# Display.net
KiCad netlist of a schematic drawn in Altium Designer
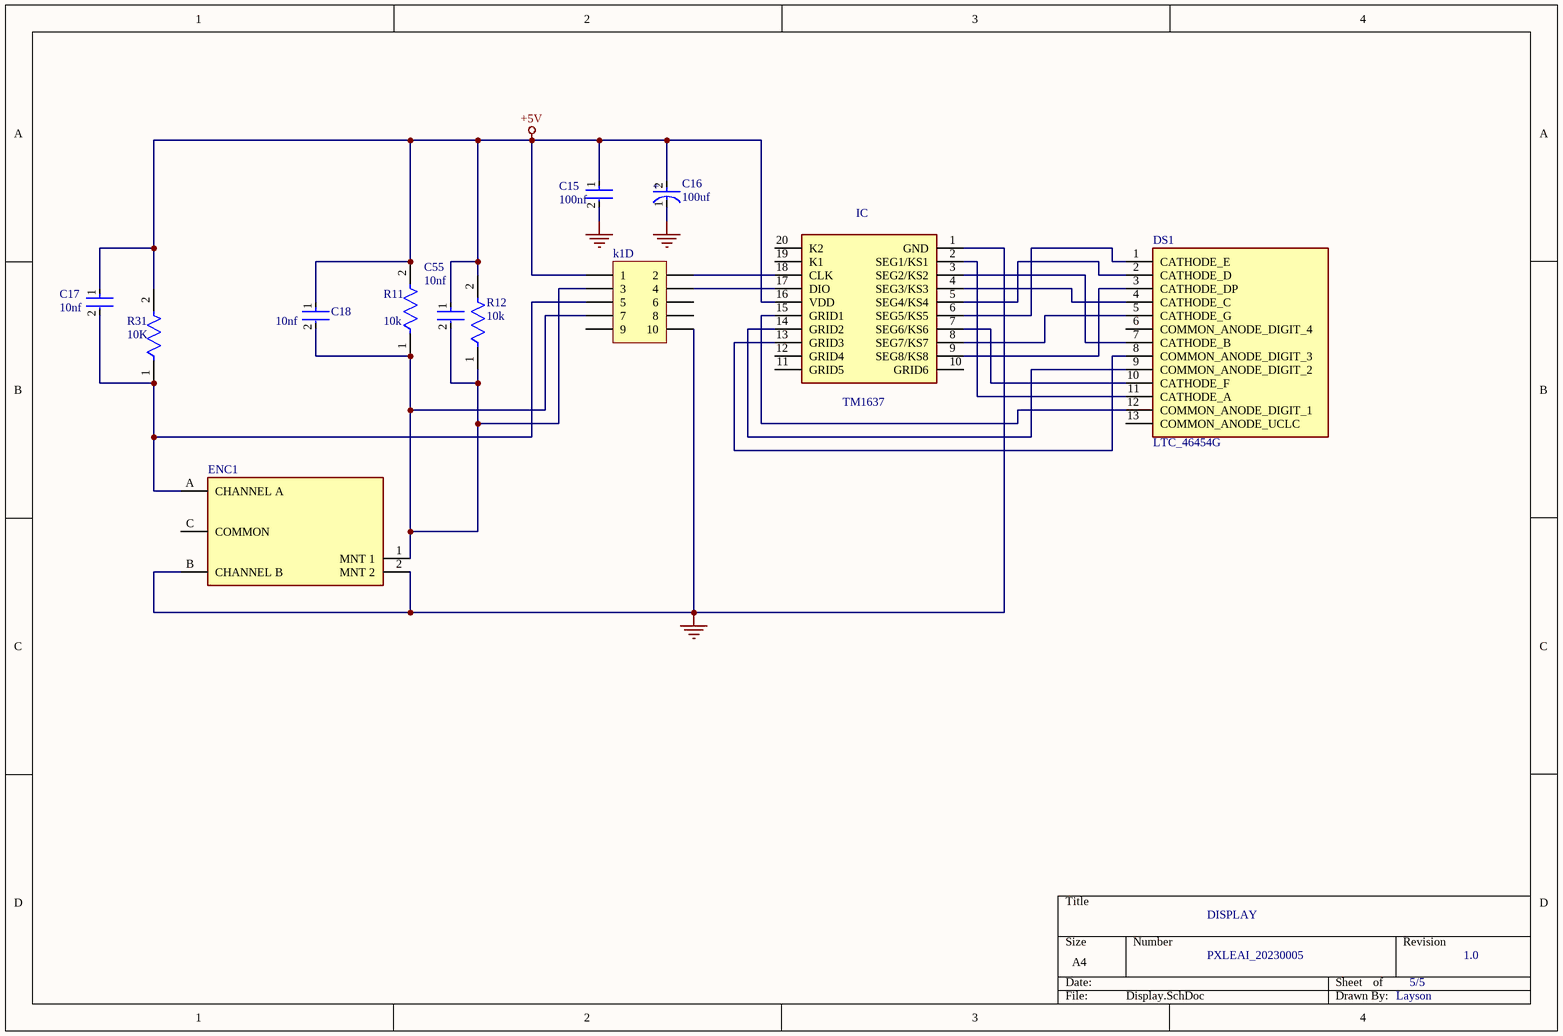
[diagram p0: Display.SchDoc]

(export (version "E")
  (design (tool "Eeschema 10.0.6"))
  (components
    (comp (ref "C15")
      (value "100nf")
      (footprint "FP-C320C-MFG")
      (description "CAP CER 0.1UF 50V X7R RADIAL")
      (fields (field (name "TOLERANCE") "5%") (field (name "MANUFACTURER PART NUMBER") "C320C104J5R5TA7301"))
      (libsource (lib "Altium Content Vault") (part "11868f565c42a9108669ba33697ecf6"))
    )
    (comp (ref "C16")
      (value "100uf")
      (footprint "FP-RAD-TH-D_8_0_5-L_11_5-MFG")
      (description "Aluminum Electrolytic Capacitors (Radial Lead Type) 100uF ±20% 50V")
      (fields (field (name "VOLTAGE") "50V") (field (name "TOLERANCE") "20%"))
      (libsource (lib "Altium Content Vault") (part "a00bbbee19879c290e62620ae7e47b1"))
    )
    (comp (ref "C17")
      (value "10nf")
      (footprint "FP-RDE0M1-MFG")
      (description "Ceramic Capacitor 10nF ±10% 50V X7R Radial")
      (fields (field (name "TOLERANCE") "10%"))
      (libsource (lib "Altium Content Vault") (part "b4654b650e69147ec39a6b967a45e02"))
    )
    (comp (ref "C18")
      (value "10nf")
      (footprint "FP-RDE0M1-MFG")
      (description "Ceramic Capacitor 10nF ±10% 50V X7R Radial")
      (fields (field (name "TOLERANCE") "10%"))
      (libsource (lib "Altium Content Vault") (part "b4654b650e69147ec39a6b967a45e02"))
    )
    (comp (ref "C55")
      (value "10nf")
      (footprint "FP-RDE0M1-MFG")
      (description "Ceramic Capacitor 10nF ±10% 50V X7R Radial")
      (fields (field (name "TOLERANCE") "10%"))
      (libsource (lib "Altium Content Vault") (part "b4654b650e69147ec39a6b967a45e02"))
    )
    (comp (ref "DS1")
      (value "LTC_46454G")
      (footprint "SamacSys:LTC46454G")
      (description "Display")
      (fields (field (name "MANUFACTURER_PART_NUMBER") "LTC 46454G"))
      (libsource (lib "*") (part "LTC_46454G"))
    )
    (comp (ref "ENC1")
      (value "PEC11R-4015F-N0024")
      (footprint "FP-PEC11R-4015F-N0024-MFG")
      (description "ROTARY ENCODER MECHANICAL 24PPR")
      (fields
        (field (name "MANUFACTURER") "Bourns")
        (field (name "OCTOPART") "https://octopart.com/pec11r-4015f-n0024-bourns-26648251")
      )
      (libsource (lib "Altium Content Vault") (part "714335eeadb64c170d88fa1cfc7421d"))
    )
    (comp (ref "IC")
      (value "TM1637")
      (footprint "SOIC127P1045X280-20N")
      (description "LED Drive Control Special Circuit")
      (fields (field (name "MANUFACTURER_PART_NUMBER") "TM1637 (SOP)"))
      (libsource (lib "Soldeerstation") (part "TM1637__SOP_"))
    )
    (comp (ref "k1D")
      (value "Header 5X2")
      (footprint "HDR2X5")
      (description "Header, 5-Pin, Dual row")
      (fields (field (name "PUBLISHER") "Altium Limited"))
      (libsource (lib "Miscellaneous Connectors") (part "Header 5X2"))
    )
    (comp (ref "R11")
      (value "10k")
      (footprint "FP-CF18-MFG")
      (description "RES 10K OHM 1/8W 5% CF AXIAL")
      (fields
        (field (name "MANUFACTURER PART NUMBER") "CF18JT10K0")
        (field (name "MANUFACTURER") "Stackpole Electronics")
      )
      (libsource (lib "Altium Content Vault") (part "1029c3af85768c4190bb7ad29bc67b5"))
    )
    (comp (ref "R12")
      (value "10k")
      (footprint "FP-CF18-MFG")
      (description "RES 10K OHM 1/8W 5% CF AXIAL")
      (fields
        (field (name "MANUFACTURER PART NUMBER") "CF18JT10K0")
        (field (name "MANUFACTURER") "Stackpole Electronics")
      )
      (libsource (lib "Altium Content Vault") (part "1029c3af85768c4190bb7ad29bc67b5"))
    )
    (comp (ref "R31")
      (value "10K")
      (footprint "FP-CF18-MFG")
      (description "RES 10K OHM 1/8W 5% CF AXIAL")
      (fields
        (field (name "MANUFACTURER PART NUMBER") "CF18JT10K0")
        (field (name "MANUFACTURER") "Stackpole Electronics")
      )
      (libsource (lib "Altium Content Vault") (part "1029c3af85768c4190bb7ad29bc67b5"))
    )
  )
  (nets
    (net (code "1") (name "+5V") (class "Default")
      (node (ref "C15") (pin "1") (pinfunction "1_1") (pintype "passive"))
      (node (ref "C16") (pin "2") (pinfunction "A_2") (pintype "passive"))
      (node (ref "C17") (pin "1") (pinfunction "1_1") (pintype "passive"))
      (node (ref "C18") (pin "1") (pinfunction "1_1") (pintype "passive"))
      (node (ref "C55") (pin "1") (pinfunction "1_1") (pintype "passive"))
      (node (ref "IC") (pin "16") (pinfunction "VDD_16") (pintype "passive"))
      (node (ref "R11") (pin "2") (pinfunction "2_2") (pintype "passive"))
      (node (ref "R12") (pin "2") (pinfunction "2_2") (pintype "passive"))
      (node (ref "R31") (pin "2") (pinfunction "2_2") (pintype "passive"))
      (node (ref "k1D") (pin "1") (pinfunction "1_1") (pintype "passive"))
    )
    (net (code "2") (name "GND") (class "Default")
      (node (ref "C15") (pin "2") (pinfunction "2_2") (pintype "passive"))
      (node (ref "C16") (pin "1") (pinfunction "C_1") (pintype "passive"))
      (node (ref "ENC1") (pin "2") (pinfunction "MNT_2_2") (pintype "passive"))
      (node (ref "ENC1") (pin "B") (pinfunction "CHANNEL_B_B") (pintype "passive"))
      (node (ref "IC") (pin "1") (pinfunction "GND_1") (pintype "passive"))
      (node (ref "k1D") (pin "10") (pinfunction "10_10") (pintype "passive"))
    )
    (net (code "3") (name "Net-(DS1-CATHODE_A)") (class "Default")
      (node (ref "DS1") (pin "11") (pinfunction "CATHODE_A_11") (pintype "passive"))
      (node (ref "IC") (pin "2") (pinfunction "SEG1/KS1_2") (pintype "passive"))
    )
    (net (code "4") (name "Net-(DS1-CATHODE_B)") (class "Default")
      (node (ref "DS1") (pin "7") (pinfunction "CATHODE_B_7") (pintype "passive"))
      (node (ref "IC") (pin "3") (pinfunction "SEG2/KS2_3") (pintype "passive"))
    )
    (net (code "5") (name "Net-(DS1-CATHODE_C)") (class "Default")
      (node (ref "DS1") (pin "4") (pinfunction "CATHODE_C_4") (pintype "passive"))
      (node (ref "IC") (pin "4") (pinfunction "SEG3/KS3_4") (pintype "passive"))
    )
    (net (code "6") (name "Net-(DS1-CATHODE_D)") (class "Default")
      (node (ref "DS1") (pin "2") (pinfunction "CATHODE_D_2") (pintype "passive"))
      (node (ref "IC") (pin "5") (pinfunction "SEG4/KS4_5") (pintype "passive"))
    )
    (net (code "7") (name "Net-(DS1-CATHODE_DP)") (class "Default")
      (node (ref "DS1") (pin "3") (pinfunction "CATHODE_DP_3") (pintype "passive"))
      (node (ref "IC") (pin "9") (pinfunction "SEG8/KS8_9") (pintype "passive"))
    )
    (net (code "8") (name "Net-(DS1-CATHODE_E)") (class "Default")
      (node (ref "DS1") (pin "1") (pinfunction "CATHODE_E_1") (pintype "passive"))
      (node (ref "IC") (pin "6") (pinfunction "SEG5/KS5_6") (pintype "passive"))
    )
    (net (code "9") (name "Net-(DS1-CATHODE_F)") (class "Default")
      (node (ref "DS1") (pin "10") (pinfunction "CATHODE_F_10") (pintype "passive"))
      (node (ref "IC") (pin "7") (pinfunction "SEG6/KS6_7") (pintype "passive"))
    )
    (net (code "10") (name "Net-(DS1-CATHODE_G)") (class "Default")
      (node (ref "DS1") (pin "5") (pinfunction "CATHODE_G_5") (pintype "passive"))
      (node (ref "IC") (pin "8") (pinfunction "SEG7/KS7_8") (pintype "passive"))
    )
    (net (code "11") (name "Net-(DS1-COMMON_ANODE_DIGIT_1)") (class "Default")
      (node (ref "DS1") (pin "12") (pinfunction "COMMON_ANODE_DIGIT_1_12") (pintype "passive"))
      (node (ref "IC") (pin "15") (pinfunction "GRID1_15") (pintype "passive"))
    )
    (net (code "12") (name "Net-(DS1-COMMON_ANODE_DIGIT_2)") (class "Default")
      (node (ref "DS1") (pin "9") (pinfunction "COMMON_ANODE_DIGIT_2_9") (pintype "passive"))
      (node (ref "IC") (pin "14") (pinfunction "GRID2_14") (pintype "passive"))
    )
    (net (code "13") (name "Net-(DS1-COMMON_ANODE_DIGIT_3)") (class "Default")
      (node (ref "DS1") (pin "8") (pinfunction "COMMON_ANODE_DIGIT_3_8") (pintype "passive"))
      (node (ref "IC") (pin "13") (pinfunction "GRID3_13") (pintype "passive"))
    )
    (net (code "14") (name "Net-(ENC1-CHANNEL_A)") (class "Default")
      (node (ref "C17") (pin "2") (pinfunction "2_2") (pintype "passive"))
      (node (ref "ENC1") (pin "A") (pinfunction "CHANNEL_A_A") (pintype "passive"))
      (node (ref "R31") (pin "1") (pinfunction "1_1") (pintype "passive"))
      (node (ref "k1D") (pin "5") (pinfunction "5_5") (pintype "passive"))
    )
    (net (code "15") (name "Net-(ENC1-MNT_1)") (class "Default")
      (node (ref "C18") (pin "2") (pinfunction "2_2") (pintype "passive"))
      (node (ref "C55") (pin "2") (pinfunction "2_2") (pintype "passive"))
      (node (ref "ENC1") (pin "1") (pinfunction "MNT_1_1") (pintype "passive"))
      (node (ref "R11") (pin "1") (pinfunction "1_1") (pintype "passive"))
      (node (ref "R12") (pin "1") (pinfunction "1_1") (pintype "passive"))
      (node (ref "k1D") (pin "3") (pinfunction "3_3") (pintype "passive"))
      (node (ref "k1D") (pin "7") (pinfunction "7_7") (pintype "passive"))
    )
    (net (code "16") (name "Net-(IC-CLK)") (class "Default")
      (node (ref "IC") (pin "18") (pinfunction "CLK_18") (pintype "passive"))
      (node (ref "k1D") (pin "2") (pinfunction "2_2") (pintype "passive"))
    )
    (net (code "17") (name "Net-(IC-DIO)") (class "Default")
      (node (ref "IC") (pin "17") (pinfunction "DIO_17") (pintype "passive"))
      (node (ref "k1D") (pin "4") (pinfunction "4_4") (pintype "passive"))
    )
    (net (code "18") (name "unconnected-(DS1-COMMON_ANODE_DIGIT_4-Pad6)") (class "Default")
      (node (ref "DS1") (pin "6") (pinfunction "COMMON_ANODE_DIGIT_4_6") (pintype "passive"))
    )
    (net (code "19") (name "unconnected-(DS1-COMMON_ANODE_UCLC-Pad13)") (class "Default")
      (node (ref "DS1") (pin "13") (pinfunction "COMMON_ANODE_UCLC_13") (pintype "passive"))
    )
    (net (code "20") (name "unconnected-(ENC1-COMMON-PadC)") (class "Default")
      (node (ref "ENC1") (pin "C") (pinfunction "COMMON_C") (pintype "passive"))
    )
    (net (code "21") (name "unconnected-(IC-GRID4-Pad12)") (class "Default")
      (node (ref "IC") (pin "12") (pinfunction "GRID4_12") (pintype "passive"))
    )
    (net (code "22") (name "unconnected-(IC-GRID5-Pad11)") (class "Default")
      (node (ref "IC") (pin "11") (pinfunction "GRID5_11") (pintype "passive"))
    )
    (net (code "23") (name "unconnected-(IC-GRID6-Pad10)") (class "Default")
      (node (ref "IC") (pin "10") (pinfunction "GRID6_10") (pintype "passive"))
    )
    (net (code "24") (name "unconnected-(IC-K1-Pad19)") (class "Default")
      (node (ref "IC") (pin "19") (pinfunction "K1_19") (pintype "passive"))
    )
    (net (code "25") (name "unconnected-(IC-K2-Pad20)") (class "Default")
      (node (ref "IC") (pin "20") (pinfunction "K2_20") (pintype "passive"))
    )
    (net (code "26") (name "unconnected-(k1D-Pad6)") (class "Default")
      (node (ref "k1D") (pin "6") (pinfunction "6_6") (pintype "passive"))
    )
    (net (code "27") (name "unconnected-(k1D-Pad8)") (class "Default")
      (node (ref "k1D") (pin "8") (pinfunction "8_8") (pintype "passive"))
    )
    (net (code "28") (name "unconnected-(k1D-Pad9)") (class "Default")
      (node (ref "k1D") (pin "9") (pinfunction "9_9") (pintype "passive"))
    )
  )
)
